# 07_Indicators.net
KiCad netlist of a schematic drawn in Altium Designer
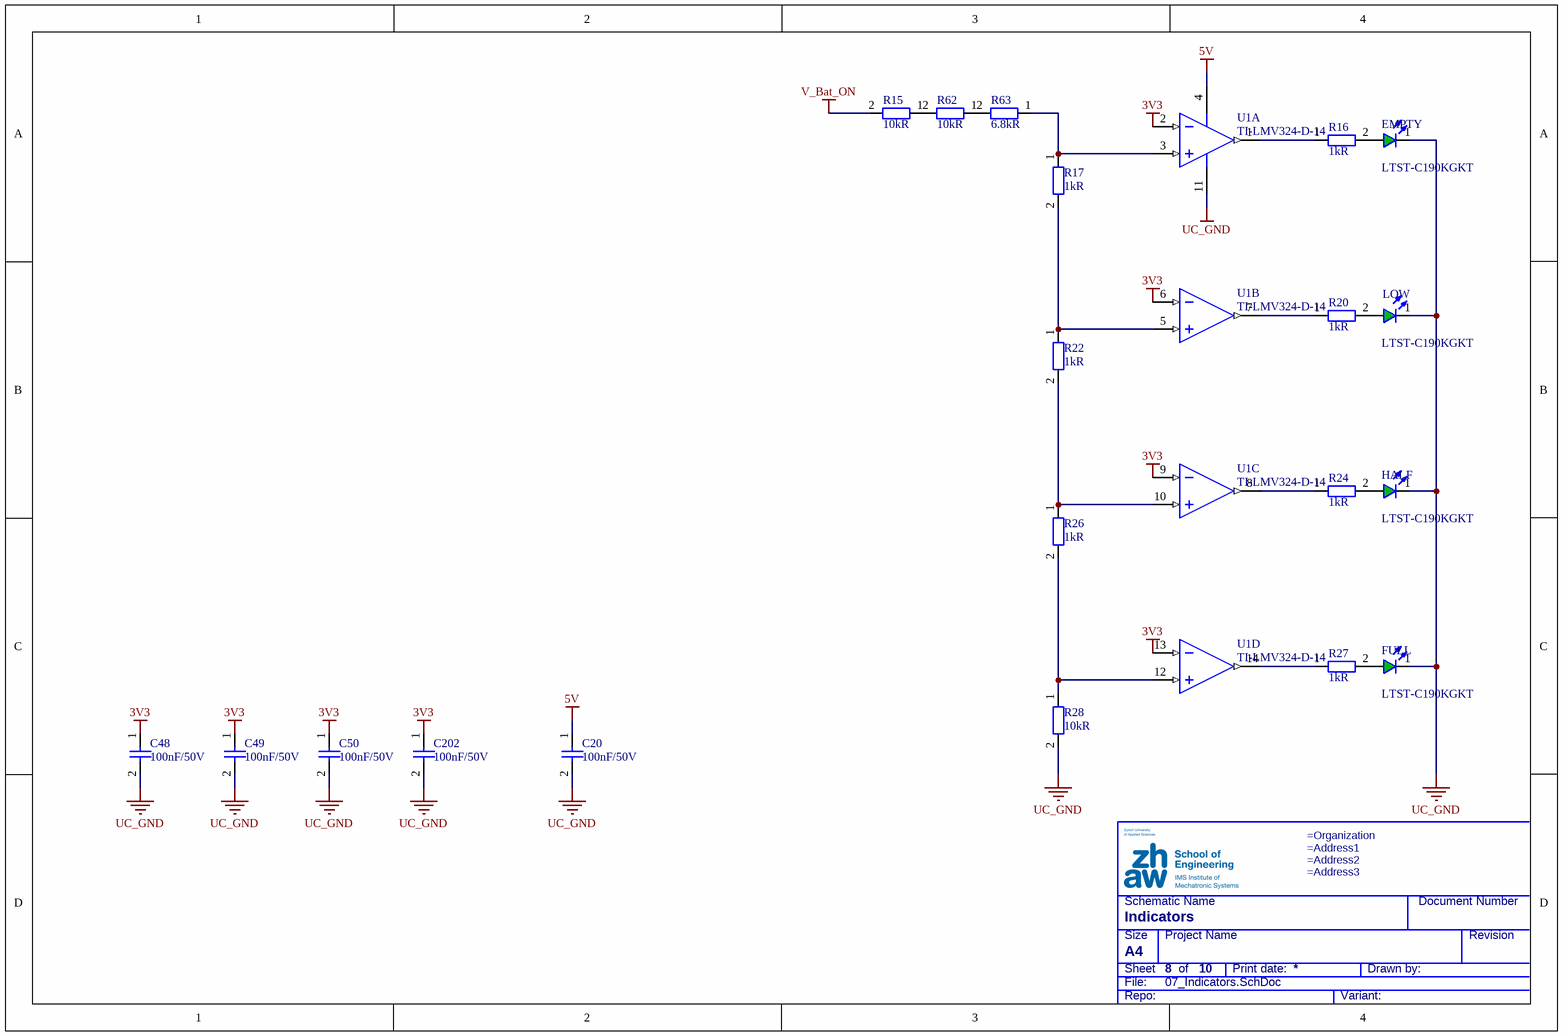
[diagram p0: 07_Indicators.SchDoc]

(export (version "E")
  (design (tool "Eeschema 10.0.6"))
  (components
    (comp (ref "C20")
      (value "100nF/50V")
      (footprint "CAPC1005X05L")
      (description "Cap MLCC, 100nF, 50V, X7R, 10%, 0402")
      (fields (field (name "TOLERANCE") "10%"))
      (libsource (lib "Altium Concord Pro on Altium 365") (part "CAP-NP-2"))
    )
    (comp (ref "C48")
      (value "100nF/50V")
      (footprint "CAPC1005X05L")
      (description "Cap MLCC, 100nF, 50V, X7R, 10%, 0402")
      (fields (field (name "TOLERANCE") "10%"))
      (libsource (lib "Altium Concord Pro on Altium 365") (part "CAP-NP-2"))
    )
    (comp (ref "C49")
      (value "100nF/50V")
      (footprint "CAPC1005X05L")
      (description "Cap MLCC, 100nF, 50V, X7R, 10%, 0402")
      (fields (field (name "TOLERANCE") "10%"))
      (libsource (lib "Altium Concord Pro on Altium 365") (part "CAP-NP-2"))
    )
    (comp (ref "C50")
      (value "100nF/50V")
      (footprint "CAPC1005X05L")
      (description "Cap MLCC, 100nF, 50V, X7R, 10%, 0402")
      (fields (field (name "TOLERANCE") "10%"))
      (libsource (lib "Altium Concord Pro on Altium 365") (part "CAP-NP-2"))
    )
    (comp (ref "C202")
      (value "100nF/50V")
      (footprint "CAPC1005X05L")
      (description "Cap MLCC, 100nF, 50V, X7R, 10%, 0402")
      (fields (field (name "TOLERANCE") "10%"))
      (libsource (lib "Altium Concord Pro on Altium 365") (part "CAP-NP-2"))
    )
    (comp (ref "EMPTY")
      (value "LTST-C190KGKT")
      (footprint "LEDSC160X80X80-2Lgn")
      (description "LED, Green, 20mA, 2.0V, 0603")
      (libsource (lib "Altium Concord Pro on Altium 365") (part "LED-GREEN-AK-2"))
    )
    (comp (ref "FULL")
      (value "LTST-C190KGKT")
      (footprint "LEDSC160X80X80-2Lgn")
      (description "LED, Green, 20mA, 2.0V, 0603")
      (libsource (lib "Altium Concord Pro on Altium 365") (part "LED-GREEN-AK-2"))
    )
    (comp (ref "HALF")
      (value "LTST-C190KGKT")
      (footprint "LEDSC160X80X80-2Lgn")
      (description "LED, Green, 20mA, 2.0V, 0603")
      (libsource (lib "Altium Concord Pro on Altium 365") (part "LED-GREEN-AK-2"))
    )
    (comp (ref "LOW")
      (value "LTST-C190KGKT")
      (footprint "LEDSC160X80X80-2Lgn")
      (description "LED, Green, 20mA, 2.0V, 0603")
      (libsource (lib "Altium Concord Pro on Altium 365") (part "LED-GREEN-AK-2"))
    )
    (comp (ref "R15")
      (value "10kR")
      (footprint "RESC1005X04L")
      (description "Res, 10kR, 1%, 0.1W, 0402")
      (fields (field (name "POWER") "100mW") (field (name "TOLERANCE") "1%"))
      (libsource (lib "Altium Concord Pro on Altium 365") (part "RES-2"))
    )
    (comp (ref "R16")
      (value "1kR")
      (footprint "RESC1005X04L")
      (description "Res, 1kR, 1%, 0.1W, 0402")
      (fields (field (name "POWER") "100mW") (field (name "TOLERANCE") "1%"))
      (libsource (lib "") (part "RES-2_2"))
    )
    (comp (ref "R17")
      (value "1kR")
      (footprint "RESC1005X04L")
      (description "Res, 1kR, 1%, 0.1W, 0402")
      (fields (field (name "POWER") "100mW") (field (name "TOLERANCE") "1%"))
      (libsource (lib "") (part "RES-2_1"))
    )
    (comp (ref "R20")
      (value "1kR")
      (footprint "RESC1005X04L")
      (description "Res, 1kR, 1%, 0.1W, 0402")
      (fields (field (name "POWER") "100mW") (field (name "TOLERANCE") "1%"))
      (libsource (lib "") (part "RES-2_2"))
    )
    (comp (ref "R22")
      (value "1kR")
      (footprint "RESC1005X04L")
      (description "Res, 1kR, 1%, 0.1W, 0402")
      (fields (field (name "POWER") "100mW") (field (name "TOLERANCE") "1%"))
      (libsource (lib "") (part "RES-2_1"))
    )
    (comp (ref "R24")
      (value "1kR")
      (footprint "RESC1005X04L")
      (description "Res, 1kR, 1%, 0.1W, 0402")
      (fields (field (name "POWER") "100mW") (field (name "TOLERANCE") "1%"))
      (libsource (lib "") (part "RES-2_2"))
    )
    (comp (ref "R26")
      (value "1kR")
      (footprint "RESC1005X04L")
      (description "Res, 1kR, 1%, 0.1W, 0402")
      (fields (field (name "POWER") "100mW") (field (name "TOLERANCE") "1%"))
      (libsource (lib "") (part "RES-2_1"))
    )
    (comp (ref "R27")
      (value "1kR")
      (footprint "RESC1005X04L")
      (description "Res, 1kR, 1%, 0.1W, 0402")
      (fields (field (name "POWER") "100mW") (field (name "TOLERANCE") "1%"))
      (libsource (lib "") (part "RES-2_2"))
    )
    (comp (ref "R28")
      (value "10kR")
      (footprint "RESC1005X04L")
      (description "Res, 10kR, 1%, 0.1W, 0402")
      (fields (field (name "POWER") "100mW") (field (name "TOLERANCE") "1%"))
      (libsource (lib "") (part "RES-2_1"))
    )
    (comp (ref "R62")
      (value "10kR")
      (footprint "RESC1005X04L")
      (description "Res, 10kR, 1%, 0.1W, 0402")
      (fields (field (name "POWER") "100mW") (field (name "TOLERANCE") "1%"))
      (libsource (lib "Altium Concord Pro on Altium 365") (part "RES-2"))
    )
    (comp (ref "R63")
      (value "6.8kR")
      (footprint "RESC1005X04L")
      (description "Res, 6.8kR, 1%, 0.063W, 0402")
      (fields (field (name "POWER") "63mW") (field (name "TOLERANCE") "1%"))
      (libsource (lib "Altium Concord Pro on Altium 365") (part "RES-2"))
    )
    (comp (ref "U1")
      (value "TI-LMV324-D-14")
      (footprint "D0014A_V")
      (description "OP 4 Ch, 2.7..5.5V, 1MHz, 1V/us, R2R: Out, SOIC-14")
      (libsource (lib "Altium Concord Pro on Altium 365") (part "TI-LMV324-D-14"))
    )
  )
  (nets
    (net (code "1") (name "3V3") (class "Default")
      (node (ref "C202") (pin "1") (pinfunction "1_1") (pintype "passive"))
      (node (ref "C48") (pin "1") (pinfunction "1_1") (pintype "passive"))
      (node (ref "C49") (pin "1") (pinfunction "1_1") (pintype "passive"))
      (node (ref "C50") (pin "1") (pinfunction "1_1") (pintype "passive"))
      (node (ref "U1") (pin "13") (pinfunction "4IN-_13") (pintype "input"))
      (node (ref "U1") (pin "2") (pinfunction "1IN-_2") (pintype "input"))
      (node (ref "U1") (pin "6") (pinfunction "2IN-_6") (pintype "input"))
      (node (ref "U1") (pin "9") (pinfunction "3IN-_9") (pintype "input"))
    )
    (net (code "2") (name "5V") (class "Default")
      (node (ref "C20") (pin "1") (pinfunction "1_1") (pintype "passive"))
      (node (ref "U1") (pin "4") (pinfunction "VCC+_4") (pintype "power_in"))
    )
    (net (code "3") (name "Net-(EMPTY-A)") (class "Default")
      (node (ref "EMPTY") (pin "2") (pinfunction "A_2") (pintype "passive"))
      (node (ref "R16") (pin "2") (pinfunction "2_2") (pintype "passive"))
    )
    (net (code "4") (name "Net-(FULL-A)") (class "Default")
      (node (ref "FULL") (pin "2") (pinfunction "A_2") (pintype "passive"))
      (node (ref "R27") (pin "2") (pinfunction "2_2") (pintype "passive"))
    )
    (net (code "5") (name "Net-(HALF-A)") (class "Default")
      (node (ref "HALF") (pin "2") (pinfunction "A_2") (pintype "passive"))
      (node (ref "R24") (pin "2") (pinfunction "2_2") (pintype "passive"))
    )
    (net (code "6") (name "Net-(LOW-A)") (class "Default")
      (node (ref "LOW") (pin "2") (pinfunction "A_2") (pintype "passive"))
      (node (ref "R20") (pin "2") (pinfunction "2_2") (pintype "passive"))
    )
    (net (code "7") (name "Net-(R15-Pad1)") (class "Default")
      (node (ref "R15") (pin "1") (pinfunction "1_1") (pintype "passive"))
      (node (ref "R62") (pin "2") (pinfunction "2_2") (pintype "passive"))
    )
    (net (code "8") (name "Net-(R62-Pad1)") (class "Default")
      (node (ref "R62") (pin "1") (pinfunction "1_1") (pintype "passive"))
      (node (ref "R63") (pin "2") (pinfunction "2_2") (pintype "passive"))
    )
    (net (code "9") (name "Net-(U1A-1IN+)") (class "Default")
      (node (ref "R17") (pin "1") (pinfunction "1_1") (pintype "passive"))
      (node (ref "R63") (pin "1") (pinfunction "1_1") (pintype "passive"))
      (node (ref "U1") (pin "3") (pinfunction "1IN+_3") (pintype "input"))
    )
    (net (code "10") (name "Net-(U1A-1OUT)") (class "Default")
      (node (ref "R16") (pin "1") (pinfunction "1_1") (pintype "passive"))
      (node (ref "U1") (pin "1") (pinfunction "1OUT_1") (pintype "output"))
    )
    (net (code "11") (name "Net-(U1B-2IN+)") (class "Default")
      (node (ref "R17") (pin "2") (pinfunction "2_2") (pintype "passive"))
      (node (ref "R22") (pin "1") (pinfunction "1_1") (pintype "passive"))
      (node (ref "U1") (pin "5") (pinfunction "2IN+_5") (pintype "input"))
    )
    (net (code "12") (name "Net-(U1B-2OUT)") (class "Default")
      (node (ref "R20") (pin "1") (pinfunction "1_1") (pintype "passive"))
      (node (ref "U1") (pin "7") (pinfunction "2OUT_7") (pintype "output"))
    )
    (net (code "13") (name "Net-(U1C-3IN+)") (class "Default")
      (node (ref "R22") (pin "2") (pinfunction "2_2") (pintype "passive"))
      (node (ref "R26") (pin "1") (pinfunction "1_1") (pintype "passive"))
      (node (ref "U1") (pin "10") (pinfunction "3IN+_10") (pintype "input"))
    )
    (net (code "14") (name "Net-(U1C-3OUT)") (class "Default")
      (node (ref "R24") (pin "1") (pinfunction "1_1") (pintype "passive"))
      (node (ref "U1") (pin "8") (pinfunction "3OUT_8") (pintype "output"))
    )
    (net (code "15") (name "Net-(U1D-4IN+)") (class "Default")
      (node (ref "R26") (pin "2") (pinfunction "2_2") (pintype "passive"))
      (node (ref "R28") (pin "1") (pinfunction "1_1") (pintype "passive"))
      (node (ref "U1") (pin "12") (pinfunction "4IN+_12") (pintype "input"))
    )
    (net (code "16") (name "Net-(U1D-4OUT)") (class "Default")
      (node (ref "R27") (pin "1") (pinfunction "1_1") (pintype "passive"))
      (node (ref "U1") (pin "14") (pinfunction "4OUT_14") (pintype "output"))
    )
    (net (code "17") (name "UC_GND") (class "Default")
      (node (ref "C20") (pin "2") (pinfunction "2_2") (pintype "passive"))
      (node (ref "C202") (pin "2") (pinfunction "2_2") (pintype "passive"))
      (node (ref "C48") (pin "2") (pinfunction "2_2") (pintype "passive"))
      (node (ref "C49") (pin "2") (pinfunction "2_2") (pintype "passive"))
      (node (ref "C50") (pin "2") (pinfunction "2_2") (pintype "passive"))
      (node (ref "EMPTY") (pin "1") (pinfunction "K_1") (pintype "passive"))
      (node (ref "FULL") (pin "1") (pinfunction "K_1") (pintype "passive"))
      (node (ref "HALF") (pin "1") (pinfunction "K_1") (pintype "passive"))
      (node (ref "LOW") (pin "1") (pinfunction "K_1") (pintype "passive"))
      (node (ref "R28") (pin "2") (pinfunction "2_2") (pintype "passive"))
      (node (ref "U1") (pin "11") (pinfunction "GND_11") (pintype "power_in"))
    )
    (net (code "18") (name "V_Bat_ON") (class "Default")
      (node (ref "R15") (pin "2") (pinfunction "2_2") (pintype "passive"))
    )
  )
)
